# R141D.net
KiCad netlist of a schematic drawn in EAGLE
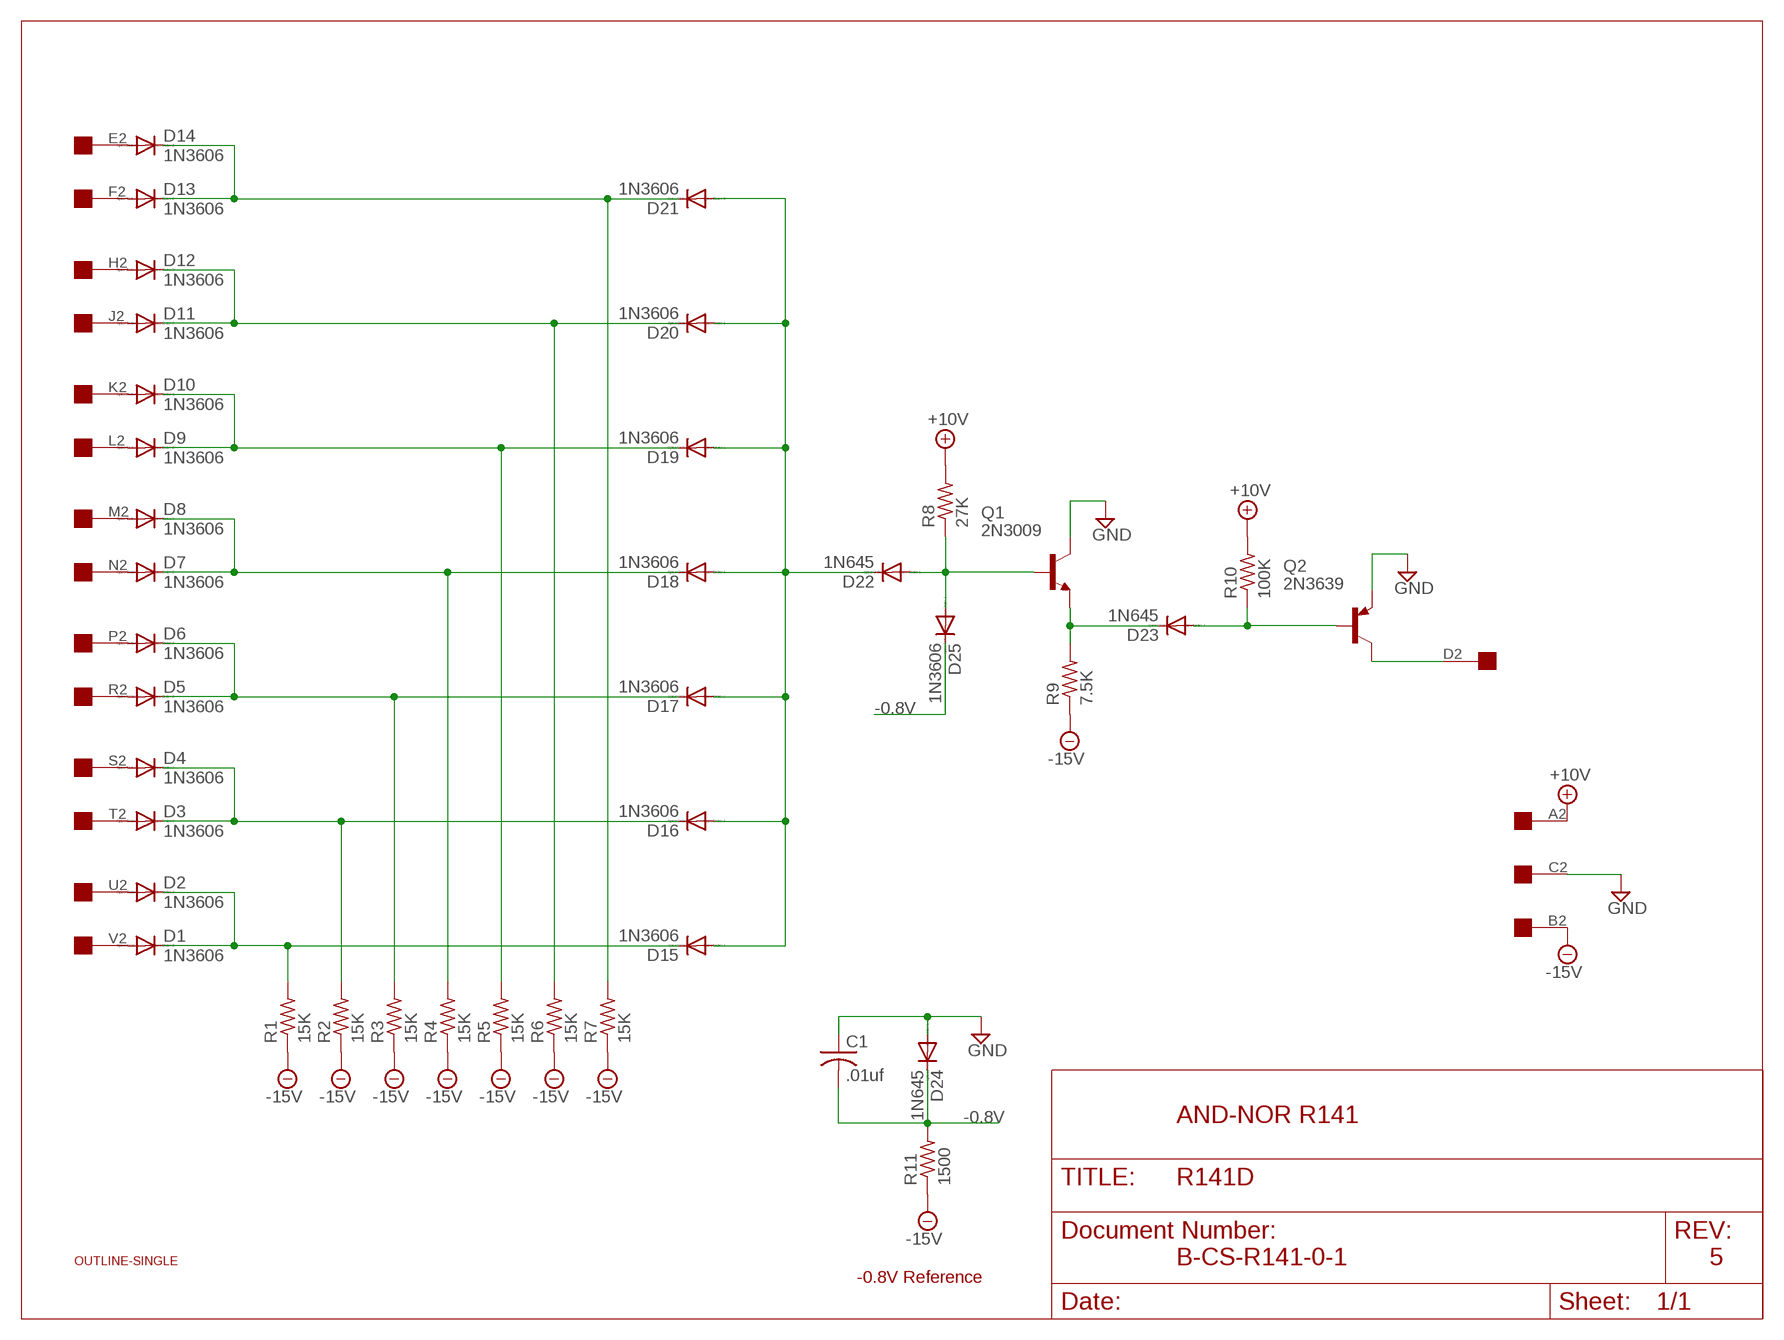
[diagram p0: schematic, sheet 1]

(export (version "E")
  (design (tool "Eeschema 10.0.6"))
  (components
    (comp (ref "C1")
      (value ".01uf")
      (footprint "eagle-import:C063-025X075")
      (libsource (lib "eagle-import") (part "C-US"))
    )
    (comp (ref "D1")
      (value "1N3606")
      (footprint "eagle-import:DO35-10")
      (libsource (lib "eagle-import") (part "1N4148DO35-10"))
    )
    (comp (ref "D2")
      (value "1N3606")
      (footprint "eagle-import:DO35-10")
      (libsource (lib "eagle-import") (part "1N4148DO35-10"))
    )
    (comp (ref "D3")
      (value "1N3606")
      (footprint "eagle-import:DO35-10")
      (libsource (lib "eagle-import") (part "1N4148DO35-10"))
    )
    (comp (ref "D4")
      (value "1N3606")
      (footprint "eagle-import:DO35-10")
      (libsource (lib "eagle-import") (part "1N4148DO35-10"))
    )
    (comp (ref "D5")
      (value "1N3606")
      (footprint "eagle-import:DO35-10")
      (libsource (lib "eagle-import") (part "1N4148DO35-10"))
    )
    (comp (ref "D6")
      (value "1N3606")
      (footprint "eagle-import:DO35-10")
      (libsource (lib "eagle-import") (part "1N4148DO35-10"))
    )
    (comp (ref "D7")
      (value "1N3606")
      (footprint "eagle-import:DO35-10")
      (libsource (lib "eagle-import") (part "1N4148DO35-10"))
    )
    (comp (ref "D8")
      (value "1N3606")
      (footprint "eagle-import:DO35-10")
      (libsource (lib "eagle-import") (part "1N4148DO35-10"))
    )
    (comp (ref "D9")
      (value "1N3606")
      (footprint "eagle-import:DO35-10")
      (libsource (lib "eagle-import") (part "1N4148DO35-10"))
    )
    (comp (ref "D10")
      (value "1N3606")
      (footprint "eagle-import:DO35-10")
      (libsource (lib "eagle-import") (part "1N4148DO35-10"))
    )
    (comp (ref "D11")
      (value "1N3606")
      (footprint "eagle-import:DO35-10")
      (libsource (lib "eagle-import") (part "1N4148DO35-10"))
    )
    (comp (ref "D12")
      (value "1N3606")
      (footprint "eagle-import:DO35-10")
      (libsource (lib "eagle-import") (part "1N4148DO35-10"))
    )
    (comp (ref "D13")
      (value "1N3606")
      (footprint "eagle-import:DO35-10")
      (libsource (lib "eagle-import") (part "1N4148DO35-10"))
    )
    (comp (ref "D14")
      (value "1N3606")
      (footprint "eagle-import:DO35-10")
      (libsource (lib "eagle-import") (part "1N4148DO35-10"))
    )
    (comp (ref "D15")
      (value "1N3606")
      (footprint "eagle-import:DO35-10")
      (libsource (lib "eagle-import") (part "1N4148DO35-10"))
    )
    (comp (ref "D16")
      (value "1N3606")
      (footprint "eagle-import:DO35-10")
      (libsource (lib "eagle-import") (part "1N4148DO35-10"))
    )
    (comp (ref "D17")
      (value "1N3606")
      (footprint "eagle-import:DO35-10")
      (libsource (lib "eagle-import") (part "1N4148DO35-10"))
    )
    (comp (ref "D18")
      (value "1N3606")
      (footprint "eagle-import:DO35-10")
      (libsource (lib "eagle-import") (part "1N4148DO35-10"))
    )
    (comp (ref "D19")
      (value "1N3606")
      (footprint "eagle-import:DO35-10")
      (libsource (lib "eagle-import") (part "1N4148DO35-10"))
    )
    (comp (ref "D20")
      (value "1N3606")
      (footprint "eagle-import:DO35-10")
      (libsource (lib "eagle-import") (part "1N4148DO35-10"))
    )
    (comp (ref "D21")
      (value "1N3606")
      (footprint "eagle-import:DO35-10")
      (libsource (lib "eagle-import") (part "1N4148DO35-10"))
    )
    (comp (ref "D22")
      (value "1N645")
      (footprint "eagle-import:DO35-10")
      (libsource (lib "eagle-import") (part "1N4148DO35-10"))
    )
    (comp (ref "D23")
      (value "1N645")
      (footprint "eagle-import:DO35-10")
      (libsource (lib "eagle-import") (part "1N4148DO35-10"))
    )
    (comp (ref "D24")
      (value "1N645")
      (footprint "eagle-import:DO35-10")
      (libsource (lib "eagle-import") (part "1N4148DO35-10"))
    )
    (comp (ref "D25")
      (value "1N3606")
      (footprint "eagle-import:DO35-10")
      (libsource (lib "eagle-import") (part "1N4148DO35-10"))
    )
    (comp (ref "Q1")
      (value "2N3009")
      (footprint "eagle-import:TO39")
      (libsource (lib "eagle-import") (part "-NPN-TO39-EBC2N3019"))
    )
    (comp (ref "Q2")
      (value "2N3639")
      (footprint "eagle-import:TO39")
      (libsource (lib "eagle-import") (part "2N3637"))
    )
    (comp (ref "R1")
      (value "15K")
      (footprint "eagle-import:0207_10")
      (libsource (lib "eagle-import") (part "R-US_0207/10"))
    )
    (comp (ref "R2")
      (value "15K")
      (footprint "eagle-import:0207_10")
      (libsource (lib "eagle-import") (part "R-US_0207/10"))
    )
    (comp (ref "R3")
      (value "15K")
      (footprint "eagle-import:0207_10")
      (libsource (lib "eagle-import") (part "R-US_0207/10"))
    )
    (comp (ref "R4")
      (value "15K")
      (footprint "eagle-import:0207_10")
      (libsource (lib "eagle-import") (part "R-US_0207/10"))
    )
    (comp (ref "R5")
      (value "15K")
      (footprint "eagle-import:0207_10")
      (libsource (lib "eagle-import") (part "R-US_0207/10"))
    )
    (comp (ref "R6")
      (value "15K")
      (footprint "eagle-import:0207_10")
      (libsource (lib "eagle-import") (part "R-US_0207/10"))
    )
    (comp (ref "R7")
      (value "15K")
      (footprint "eagle-import:0207_10")
      (libsource (lib "eagle-import") (part "R-US_0207/10"))
    )
    (comp (ref "R8")
      (value "27K")
      (footprint "eagle-import:0207_10")
      (libsource (lib "eagle-import") (part "R-US_0207/10"))
    )
    (comp (ref "R9")
      (value "7.5K")
      (footprint "eagle-import:0207_10")
      (libsource (lib "eagle-import") (part "R-US_0207/10"))
    )
    (comp (ref "R10")
      (value "100K")
      (footprint "eagle-import:0207_10")
      (libsource (lib "eagle-import") (part "R-US_0207/10"))
    )
    (comp (ref "R11")
      (value "1500")
      (footprint "eagle-import:0207_10")
      (libsource (lib "eagle-import") (part "R-US_0207/10"))
    )
    (comp (ref "U$1")
      (value "OUTLINE-SINGLE")
      (footprint "eagle-import:SINGLE")
      (libsource (lib "eagle-import") (part "OUTLINE-SINGLE"))
    )
    (comp (ref "U$2")
      (value "EDGE-1")
      (footprint "eagle-import:EDGE-CON1")
      (libsource (lib "eagle-import") (part "EDGE-1"))
    )
  )
  (nets
    (net (code "1") (name "+10V") (class "Default")
      (node (ref "R10") (pin "2") (pinfunction "2_2") (pintype "passive"))
      (node (ref "R8") (pin "2") (pinfunction "2_2") (pintype "passive"))
      (node (ref "U$2") (pin "A2") (pinfunction "1_A2") (pintype "bidirectional"))
    )
    (net (code "2") (name "-15V") (class "Default")
      (node (ref "R1") (pin "1") (pinfunction "1_1") (pintype "passive"))
      (node (ref "R11") (pin "1") (pinfunction "1_1") (pintype "passive"))
      (node (ref "R2") (pin "1") (pinfunction "1_1") (pintype "passive"))
      (node (ref "R3") (pin "1") (pinfunction "1_1") (pintype "passive"))
      (node (ref "R4") (pin "1") (pinfunction "1_1") (pintype "passive"))
      (node (ref "R5") (pin "1") (pinfunction "1_1") (pintype "passive"))
      (node (ref "R6") (pin "1") (pinfunction "1_1") (pintype "passive"))
      (node (ref "R7") (pin "1") (pinfunction "1_1") (pintype "passive"))
      (node (ref "R9") (pin "1") (pinfunction "1_1") (pintype "passive"))
      (node (ref "U$2") (pin "B2") (pinfunction "1_B2") (pintype "bidirectional"))
    )
    (net (code "3") (name "/-0.8V") (class "Default")
      (node (ref "C1") (pin "2") (pinfunction "2_2") (pintype "passive"))
      (node (ref "D24") (pin "C") (pinfunction "C_C") (pintype "passive"))
      (node (ref "D25") (pin "C") (pinfunction "C_C") (pintype "passive"))
      (node (ref "R11") (pin "2") (pinfunction "2_2") (pintype "passive"))
    )
    (net (code "4") (name "GND") (class "Default")
      (node (ref "C1") (pin "1") (pinfunction "1_1") (pintype "passive"))
      (node (ref "D24") (pin "A") (pinfunction "A_A") (pintype "passive"))
      (node (ref "Q1") (pin "3") (pinfunction "C_3") (pintype "passive"))
      (node (ref "Q2") (pin "1") (pinfunction "E_1") (pintype "passive"))
      (node (ref "U$2") (pin "C2") (pinfunction "1_C2") (pintype "bidirectional"))
    )
    (net (code "5") (name "Net-(D1-PadC)") (class "Default")
      (node (ref "D1") (pin "C") (pinfunction "C_C") (pintype "passive"))
      (node (ref "D15") (pin "C") (pinfunction "C_C") (pintype "passive"))
      (node (ref "D2") (pin "C") (pinfunction "C_C") (pintype "passive"))
      (node (ref "R1") (pin "2") (pinfunction "2_2") (pintype "passive"))
    )
    (net (code "6") (name "Net-(D10-PadC)") (class "Default")
      (node (ref "D10") (pin "C") (pinfunction "C_C") (pintype "passive"))
      (node (ref "D19") (pin "C") (pinfunction "C_C") (pintype "passive"))
      (node (ref "D9") (pin "C") (pinfunction "C_C") (pintype "passive"))
      (node (ref "R5") (pin "2") (pinfunction "2_2") (pintype "passive"))
    )
    (net (code "7") (name "Net-(D11-PadC)") (class "Default")
      (node (ref "D11") (pin "C") (pinfunction "C_C") (pintype "passive"))
      (node (ref "D12") (pin "C") (pinfunction "C_C") (pintype "passive"))
      (node (ref "D20") (pin "C") (pinfunction "C_C") (pintype "passive"))
      (node (ref "R6") (pin "2") (pinfunction "2_2") (pintype "passive"))
    )
    (net (code "8") (name "Net-(D13-PadC)") (class "Default")
      (node (ref "D13") (pin "C") (pinfunction "C_C") (pintype "passive"))
      (node (ref "D14") (pin "C") (pinfunction "C_C") (pintype "passive"))
      (node (ref "D21") (pin "C") (pinfunction "C_C") (pintype "passive"))
      (node (ref "R7") (pin "2") (pinfunction "2_2") (pintype "passive"))
    )
    (net (code "9") (name "Net-(D15-PadA)") (class "Default")
      (node (ref "D15") (pin "A") (pinfunction "A_A") (pintype "passive"))
      (node (ref "D16") (pin "A") (pinfunction "A_A") (pintype "passive"))
      (node (ref "D17") (pin "A") (pinfunction "A_A") (pintype "passive"))
      (node (ref "D18") (pin "A") (pinfunction "A_A") (pintype "passive"))
      (node (ref "D19") (pin "A") (pinfunction "A_A") (pintype "passive"))
      (node (ref "D20") (pin "A") (pinfunction "A_A") (pintype "passive"))
      (node (ref "D21") (pin "A") (pinfunction "A_A") (pintype "passive"))
      (node (ref "D22") (pin "C") (pinfunction "C_C") (pintype "passive"))
    )
    (net (code "10") (name "Net-(D16-PadC)") (class "Default")
      (node (ref "D16") (pin "C") (pinfunction "C_C") (pintype "passive"))
      (node (ref "D3") (pin "C") (pinfunction "C_C") (pintype "passive"))
      (node (ref "D4") (pin "C") (pinfunction "C_C") (pintype "passive"))
      (node (ref "R2") (pin "2") (pinfunction "2_2") (pintype "passive"))
    )
    (net (code "11") (name "Net-(D17-PadC)") (class "Default")
      (node (ref "D17") (pin "C") (pinfunction "C_C") (pintype "passive"))
      (node (ref "D5") (pin "C") (pinfunction "C_C") (pintype "passive"))
      (node (ref "D6") (pin "C") (pinfunction "C_C") (pintype "passive"))
      (node (ref "R3") (pin "2") (pinfunction "2_2") (pintype "passive"))
    )
    (net (code "12") (name "Net-(D18-PadC)") (class "Default")
      (node (ref "D18") (pin "C") (pinfunction "C_C") (pintype "passive"))
      (node (ref "D7") (pin "C") (pinfunction "C_C") (pintype "passive"))
      (node (ref "D8") (pin "C") (pinfunction "C_C") (pintype "passive"))
      (node (ref "R4") (pin "2") (pinfunction "2_2") (pintype "passive"))
    )
    (net (code "13") (name "Net-(Q1-B)") (class "Default")
      (node (ref "D22") (pin "A") (pinfunction "A_A") (pintype "passive"))
      (node (ref "D25") (pin "A") (pinfunction "A_A") (pintype "passive"))
      (node (ref "Q1") (pin "2") (pinfunction "B_2") (pintype "passive"))
      (node (ref "R8") (pin "1") (pinfunction "1_1") (pintype "passive"))
    )
    (net (code "14") (name "Net-(Q1-E)") (class "Default")
      (node (ref "D23") (pin "C") (pinfunction "C_C") (pintype "passive"))
      (node (ref "Q1") (pin "1") (pinfunction "E_1") (pintype "passive"))
      (node (ref "R9") (pin "2") (pinfunction "2_2") (pintype "passive"))
    )
    (net (code "15") (name "Net-(Q2-B)") (class "Default")
      (node (ref "D23") (pin "A") (pinfunction "A_A") (pintype "passive"))
      (node (ref "Q2") (pin "2") (pinfunction "B_2") (pintype "passive"))
      (node (ref "R10") (pin "1") (pinfunction "1_1") (pintype "passive"))
    )
    (net (code "16") (name "Net-(Q2-C)") (class "Default")
      (node (ref "Q2") (pin "3") (pinfunction "C_3") (pintype "passive"))
      (node (ref "U$2") (pin "D2") (pinfunction "1_D2") (pintype "bidirectional"))
    )
    (net (code "17") (name "Net-(U$2E-1)") (class "Default")
      (node (ref "D14") (pin "A") (pinfunction "A_A") (pintype "passive"))
      (node (ref "U$2") (pin "E2") (pinfunction "1_E2") (pintype "bidirectional"))
    )
    (net (code "18") (name "Net-(U$2F-1)") (class "Default")
      (node (ref "D13") (pin "A") (pinfunction "A_A") (pintype "passive"))
      (node (ref "U$2") (pin "F2") (pinfunction "1_F2") (pintype "bidirectional"))
    )
    (net (code "19") (name "Net-(U$2G-1)") (class "Default")
      (node (ref "D12") (pin "A") (pinfunction "A_A") (pintype "passive"))
      (node (ref "U$2") (pin "H2") (pinfunction "1_H2") (pintype "bidirectional"))
    )
    (net (code "20") (name "Net-(U$2H-1)") (class "Default")
      (node (ref "D11") (pin "A") (pinfunction "A_A") (pintype "passive"))
      (node (ref "U$2") (pin "J2") (pinfunction "1_J2") (pintype "bidirectional"))
    )
    (net (code "21") (name "Net-(U$2I-1)") (class "Default")
      (node (ref "D10") (pin "A") (pinfunction "A_A") (pintype "passive"))
      (node (ref "U$2") (pin "K2") (pinfunction "1_K2") (pintype "bidirectional"))
    )
    (net (code "22") (name "Net-(U$2J-1)") (class "Default")
      (node (ref "D9") (pin "A") (pinfunction "A_A") (pintype "passive"))
      (node (ref "U$2") (pin "L2") (pinfunction "1_L2") (pintype "bidirectional"))
    )
    (net (code "23") (name "Net-(U$2K-1)") (class "Default")
      (node (ref "D8") (pin "A") (pinfunction "A_A") (pintype "passive"))
      (node (ref "U$2") (pin "M2") (pinfunction "1_M2") (pintype "bidirectional"))
    )
    (net (code "24") (name "Net-(U$2L-1)") (class "Default")
      (node (ref "D7") (pin "A") (pinfunction "A_A") (pintype "passive"))
      (node (ref "U$2") (pin "N2") (pinfunction "1_N2") (pintype "bidirectional"))
    )
    (net (code "25") (name "Net-(U$2M-1)") (class "Default")
      (node (ref "D6") (pin "A") (pinfunction "A_A") (pintype "passive"))
      (node (ref "U$2") (pin "P2") (pinfunction "1_P2") (pintype "bidirectional"))
    )
    (net (code "26") (name "Net-(U$2N-1)") (class "Default")
      (node (ref "D5") (pin "A") (pinfunction "A_A") (pintype "passive"))
      (node (ref "U$2") (pin "R2") (pinfunction "1_R2") (pintype "bidirectional"))
    )
    (net (code "27") (name "Net-(U$2O-1)") (class "Default")
      (node (ref "D4") (pin "A") (pinfunction "A_A") (pintype "passive"))
      (node (ref "U$2") (pin "S2") (pinfunction "1_S2") (pintype "bidirectional"))
    )
    (net (code "28") (name "Net-(U$2P-1)") (class "Default")
      (node (ref "D3") (pin "A") (pinfunction "A_A") (pintype "passive"))
      (node (ref "U$2") (pin "T2") (pinfunction "1_T2") (pintype "bidirectional"))
    )
    (net (code "29") (name "Net-(U$2Q-1)") (class "Default")
      (node (ref "D2") (pin "A") (pinfunction "A_A") (pintype "passive"))
      (node (ref "U$2") (pin "U2") (pinfunction "1_U2") (pintype "bidirectional"))
    )
    (net (code "30") (name "Net-(U$2R-1)") (class "Default")
      (node (ref "D1") (pin "A") (pinfunction "A_A") (pintype "passive"))
      (node (ref "U$2") (pin "V2") (pinfunction "1_V2") (pintype "bidirectional"))
    )
  )
)
